# Top_Level.net
KiCad netlist of a schematic drawn in Altium Designer
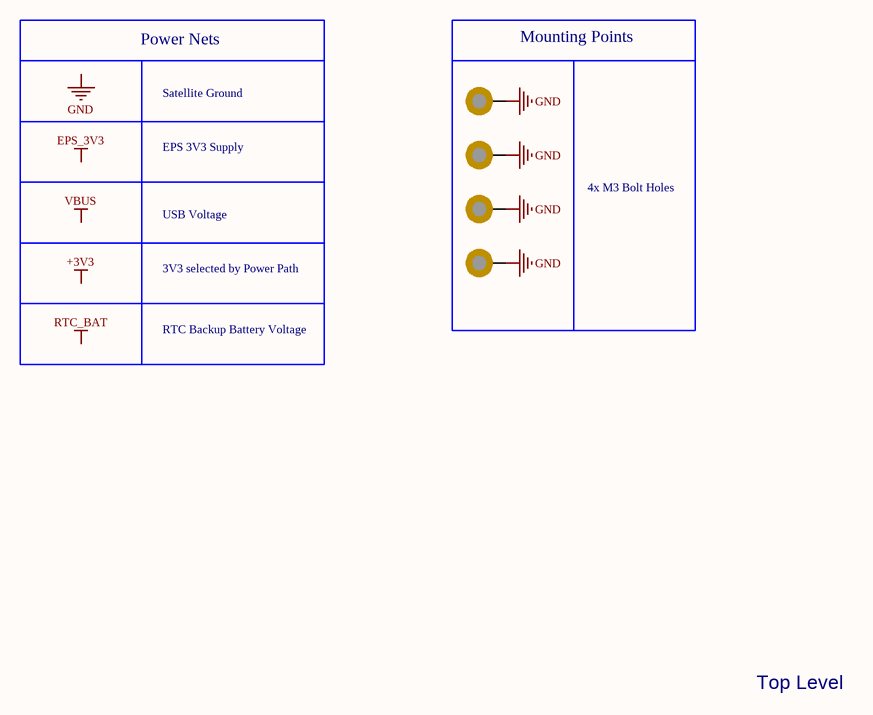
[diagram p0: Top_Level.SchDoc]

(export (version "E")
  (design (tool "Eeschema 10.0.6"))
  (components
    (comp (ref "MECH1")
      (value "M3 Mounting Hole")
      (footprint "M3 Mounting Hole")
      (libsource (lib "Ahristi_Library") (part "M3 Mounting Hole"))
    )
    (comp (ref "MECH2")
      (value "M3 Mounting Hole")
      (footprint "M3 Mounting Hole")
      (libsource (lib "Ahristi_Library") (part "M3 Mounting Hole"))
    )
    (comp (ref "MECH3")
      (value "M3 Mounting Hole")
      (footprint "M3 Mounting Hole")
      (libsource (lib "Ahristi_Library") (part "M3 Mounting Hole"))
    )
    (comp (ref "MECH4")
      (value "M3 Mounting Hole")
      (footprint "M3 Mounting Hole")
      (libsource (lib "Ahristi_Library") (part "M3 Mounting Hole"))
    )
  )
  (nets
    (net (code "3") (name "GND") (class "Default")
      (node (ref "MECH1") (pin "1") (pinfunction "1_1") (pintype "passive"))
      (node (ref "MECH2") (pin "1") (pinfunction "1_1") (pintype "passive"))
      (node (ref "MECH3") (pin "1") (pinfunction "1_1") (pintype "passive"))
      (node (ref "MECH4") (pin "1") (pinfunction "1_1") (pintype "passive"))
    )
  )
)
